# with-zener.net
KiCad netlist of a schematic drawn in EAGLE
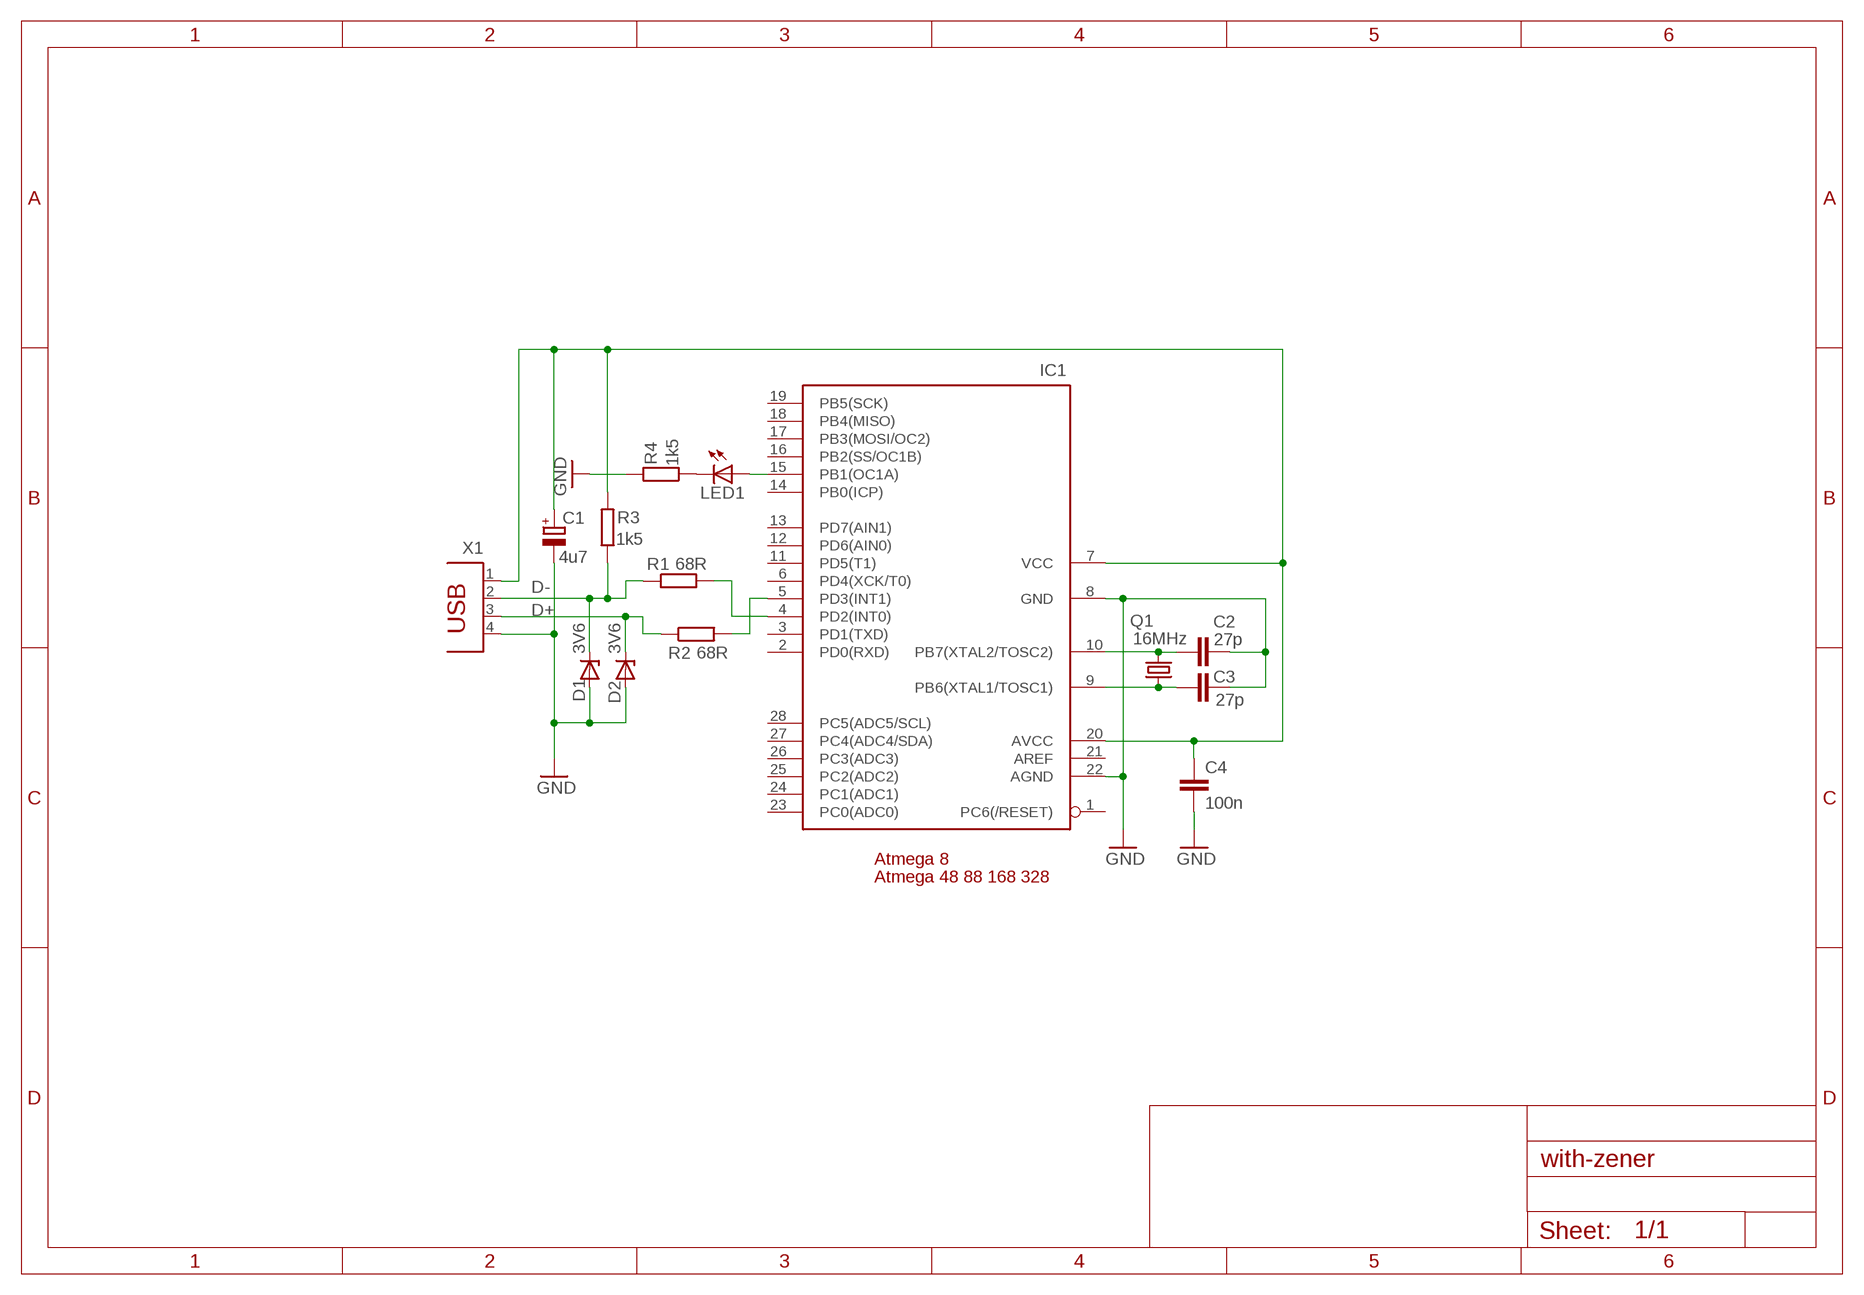
[diagram p0: schematic, sheet 1]

(export (version "E")
  (design (tool "Eeschema 10.0.6"))
  (components
    (comp (ref "C1")
      (value "4u7")
      (footprint "eagle-import:E2-5")
      (libsource (lib "eagle-import") (part "CPOL-EUE2-5"))
    )
    (comp (ref "C2")
      (value "27p")
      (footprint "eagle-import:C025-024X044")
      (libsource (lib "eagle-import") (part "C-EU025-024X044"))
    )
    (comp (ref "C3")
      (value "27p")
      (footprint "eagle-import:C025-024X044")
      (libsource (lib "eagle-import") (part "C-EU025-024X044"))
    )
    (comp (ref "C4")
      (value "100n")
      (footprint "eagle-import:C025-024X044")
      (libsource (lib "eagle-import") (part "C-EU025-024X044"))
    )
    (comp (ref "D1")
      (value "3V6")
      (footprint "eagle-import:DO34Z7")
      (libsource (lib "eagle-import") (part "ZENER-DIODEDO34-7"))
    )
    (comp (ref "D2")
      (value "3V6")
      (footprint "eagle-import:DO34Z7")
      (libsource (lib "eagle-import") (part "ZENER-DIODEDO34-7"))
    )
    (comp (ref "IC1")
      (value "ATMEGA8-16P")
      (footprint "eagle-import:DIL28-3")
      (libsource (lib "eagle-import") (part "ATMEGA8P-16"))
    )
    (comp (ref "LED1")
      (value "LED-3MM")
      (footprint "eagle-import:LED-3MM")
      (libsource (lib "eagle-import") (part "LED-3MM"))
    )
    (comp (ref "Q1")
      (value "16MHz")
      (footprint "eagle-import:HC49U-V")
      (libsource (lib "eagle-import") (part "CRYTALHC49U-V"))
    )
    (comp (ref "R1")
      (value "68R")
      (footprint "eagle-import:0207_10")
      (libsource (lib "eagle-import") (part "R-EU_0207/10"))
    )
    (comp (ref "R2")
      (value "68R")
      (footprint "eagle-import:0207_10")
      (libsource (lib "eagle-import") (part "R-EU_0207/10"))
    )
    (comp (ref "R3")
      (value "1k5")
      (footprint "eagle-import:0207_10")
      (libsource (lib "eagle-import") (part "R-EU_0207/10"))
    )
    (comp (ref "R4")
      (value "1k5")
      (footprint "eagle-import:0207_10")
      (libsource (lib "eagle-import") (part "R-EU_0207/10"))
    )
    (comp (ref "X1")
      (value "PN61729")
      (footprint "eagle-import:PN61729")
      (libsource (lib "eagle-import") (part "PN61729"))
    )
  )
  (nets
    (net (code "1") (name "/D+") (class "Default")
      (node (ref "D2") (pin "C") (pinfunction "C_C") (pintype "passive"))
      (node (ref "R2") (pin "1") (pinfunction "1_1") (pintype "passive"))
      (node (ref "X1") (pin "3") (pinfunction "3_3") (pintype "bidirectional"))
    )
    (net (code "2") (name "/D-") (class "Default")
      (node (ref "D1") (pin "C") (pinfunction "C_C") (pintype "passive"))
      (node (ref "R1") (pin "1") (pinfunction "1_1") (pintype "passive"))
      (node (ref "R3") (pin "1") (pinfunction "1_1") (pintype "passive"))
      (node (ref "X1") (pin "2") (pinfunction "2_2") (pintype "bidirectional"))
    )
    (net (code "3") (name "GND") (class "Default")
      (node (ref "C1") (pin "-") (pinfunction "-_-") (pintype "passive"))
      (node (ref "C2") (pin "2") (pinfunction "2_2") (pintype "passive"))
      (node (ref "C3") (pin "2") (pinfunction "2_2") (pintype "passive"))
      (node (ref "C4") (pin "2") (pinfunction "2_2") (pintype "passive"))
      (node (ref "D1") (pin "A") (pinfunction "A_A") (pintype "passive"))
      (node (ref "D2") (pin "A") (pinfunction "A_A") (pintype "passive"))
      (node (ref "IC1") (pin "22") (pinfunction "AGND_22") (pintype "bidirectional"))
      (node (ref "IC1") (pin "8") (pinfunction "GND_8") (pintype "bidirectional"))
      (node (ref "R4") (pin "2") (pinfunction "2_2") (pintype "passive"))
      (node (ref "X1") (pin "4") (pinfunction "4_4") (pintype "bidirectional"))
    )
    (net (code "4") (name "Net-(IC1-AVCC)") (class "Default")
      (node (ref "C1") (pin "+") (pinfunction "+_+") (pintype "passive"))
      (node (ref "C4") (pin "1") (pinfunction "1_1") (pintype "passive"))
      (node (ref "IC1") (pin "20") (pinfunction "AVCC_20") (pintype "bidirectional"))
      (node (ref "IC1") (pin "7") (pinfunction "VCC_7") (pintype "bidirectional"))
      (node (ref "R3") (pin "2") (pinfunction "2_2") (pintype "passive"))
      (node (ref "X1") (pin "1") (pinfunction "1_1") (pintype "bidirectional"))
    )
    (net (code "5") (name "Net-(IC1-PB1(OC1A))") (class "Default")
      (node (ref "IC1") (pin "15") (pinfunction "PB1(OC1A)_15") (pintype "bidirectional"))
      (node (ref "LED1") (pin "A") (pinfunction "A_A") (pintype "passive"))
    )
    (net (code "6") (name "Net-(IC1-PB6(XTAL1{slash}TOSC1))") (class "Default")
      (node (ref "C3") (pin "1") (pinfunction "1_1") (pintype "passive"))
      (node (ref "IC1") (pin "9") (pinfunction "PB6(XTAL1/TOSC1)_9") (pintype "bidirectional"))
      (node (ref "Q1") (pin "1") (pinfunction "1_1") (pintype "passive"))
    )
    (net (code "7") (name "Net-(IC1-PB7(XTAL2{slash}TOSC2))") (class "Default")
      (node (ref "C2") (pin "1") (pinfunction "1_1") (pintype "passive"))
      (node (ref "IC1") (pin "10") (pinfunction "PB7(XTAL2/TOSC2)_10") (pintype "bidirectional"))
      (node (ref "Q1") (pin "2") (pinfunction "2_2") (pintype "passive"))
    )
    (net (code "8") (name "Net-(IC1-PD2(INT0))") (class "Default")
      (node (ref "IC1") (pin "4") (pinfunction "PD2(INT0)_4") (pintype "bidirectional"))
      (node (ref "R1") (pin "2") (pinfunction "2_2") (pintype "passive"))
    )
    (net (code "9") (name "Net-(IC1-PD3(INT1))") (class "Default")
      (node (ref "IC1") (pin "5") (pinfunction "PD3(INT1)_5") (pintype "bidirectional"))
      (node (ref "R2") (pin "2") (pinfunction "2_2") (pintype "passive"))
    )
    (net (code "10") (name "Net-(LED1-C)") (class "Default")
      (node (ref "LED1") (pin "K") (pinfunction "C_K") (pintype "passive"))
      (node (ref "R4") (pin "1") (pinfunction "1_1") (pintype "passive"))
    )
    (net (code "11") (name "unconnected-(IC1-AREF-Pad21)") (class "Default")
      (node (ref "IC1") (pin "21") (pinfunction "AREF_21") (pintype "bidirectional"))
    )
    (net (code "12") (name "unconnected-(IC1-PB0(ICP)-Pad14)") (class "Default")
      (node (ref "IC1") (pin "14") (pinfunction "PB0(ICP)_14") (pintype "bidirectional"))
    )
    (net (code "13") (name "unconnected-(IC1-PB2(SS{slash}OC1B)-Pad16)") (class "Default")
      (node (ref "IC1") (pin "16") (pinfunction "PB2(SS/OC1B)_16") (pintype "bidirectional"))
    )
    (net (code "14") (name "unconnected-(IC1-PB3(MOSI{slash}OC2)-Pad17)") (class "Default")
      (node (ref "IC1") (pin "17") (pinfunction "PB3(MOSI/OC2)_17") (pintype "bidirectional"))
    )
    (net (code "15") (name "unconnected-(IC1-PB4(MISO)-Pad18)") (class "Default")
      (node (ref "IC1") (pin "18") (pinfunction "PB4(MISO)_18") (pintype "bidirectional"))
    )
    (net (code "16") (name "unconnected-(IC1-PB5(SCK)-Pad19)") (class "Default")
      (node (ref "IC1") (pin "19") (pinfunction "PB5(SCK)_19") (pintype "bidirectional"))
    )
    (net (code "17") (name "unconnected-(IC1-PC0(ADC0)-Pad23)") (class "Default")
      (node (ref "IC1") (pin "23") (pinfunction "PC0(ADC0)_23") (pintype "bidirectional"))
    )
    (net (code "18") (name "unconnected-(IC1-PC1(ADC1)-Pad24)") (class "Default")
      (node (ref "IC1") (pin "24") (pinfunction "PC1(ADC1)_24") (pintype "bidirectional"))
    )
    (net (code "19") (name "unconnected-(IC1-PC2(ADC2)-Pad25)") (class "Default")
      (node (ref "IC1") (pin "25") (pinfunction "PC2(ADC2)_25") (pintype "bidirectional"))
    )
    (net (code "20") (name "unconnected-(IC1-PC3(ADC3)-Pad26)") (class "Default")
      (node (ref "IC1") (pin "26") (pinfunction "PC3(ADC3)_26") (pintype "bidirectional"))
    )
    (net (code "21") (name "unconnected-(IC1-PC4(ADC4{slash}SDA)-Pad27)") (class "Default")
      (node (ref "IC1") (pin "27") (pinfunction "PC4(ADC4/SDA)_27") (pintype "bidirectional"))
    )
    (net (code "22") (name "unconnected-(IC1-PC5(ADC5{slash}SCL)-Pad28)") (class "Default")
      (node (ref "IC1") (pin "28") (pinfunction "PC5(ADC5/SCL)_28") (pintype "bidirectional"))
    )
    (net (code "23") (name "unconnected-(IC1-PC6({slash}RESET)-Pad1)") (class "Default")
      (node (ref "IC1") (pin "1") (pinfunction "PC6(/RESET)_1") (pintype "bidirectional"))
    )
    (net (code "24") (name "unconnected-(IC1-PD0(RXD)-Pad2)") (class "Default")
      (node (ref "IC1") (pin "2") (pinfunction "PD0(RXD)_2") (pintype "bidirectional"))
    )
    (net (code "25") (name "unconnected-(IC1-PD1(TXD)-Pad3)") (class "Default")
      (node (ref "IC1") (pin "3") (pinfunction "PD1(TXD)_3") (pintype "bidirectional"))
    )
    (net (code "26") (name "unconnected-(IC1-PD4(XCK{slash}T0)-Pad6)") (class "Default")
      (node (ref "IC1") (pin "6") (pinfunction "PD4(XCK/T0)_6") (pintype "bidirectional"))
    )
    (net (code "27") (name "unconnected-(IC1-PD5(T1)-Pad11)") (class "Default")
      (node (ref "IC1") (pin "11") (pinfunction "PD5(T1)_11") (pintype "bidirectional"))
    )
    (net (code "28") (name "unconnected-(IC1-PD6(AIN0)-Pad12)") (class "Default")
      (node (ref "IC1") (pin "12") (pinfunction "PD6(AIN0)_12") (pintype "bidirectional"))
    )
    (net (code "29") (name "unconnected-(IC1-PD7(AIN1)-Pad13)") (class "Default")
      (node (ref "IC1") (pin "13") (pinfunction "PD7(AIN1)_13") (pintype "bidirectional"))
    )
  )
)
